# CustomESP32V2.net
KiCad netlist of a schematic drawn in Altium Designer
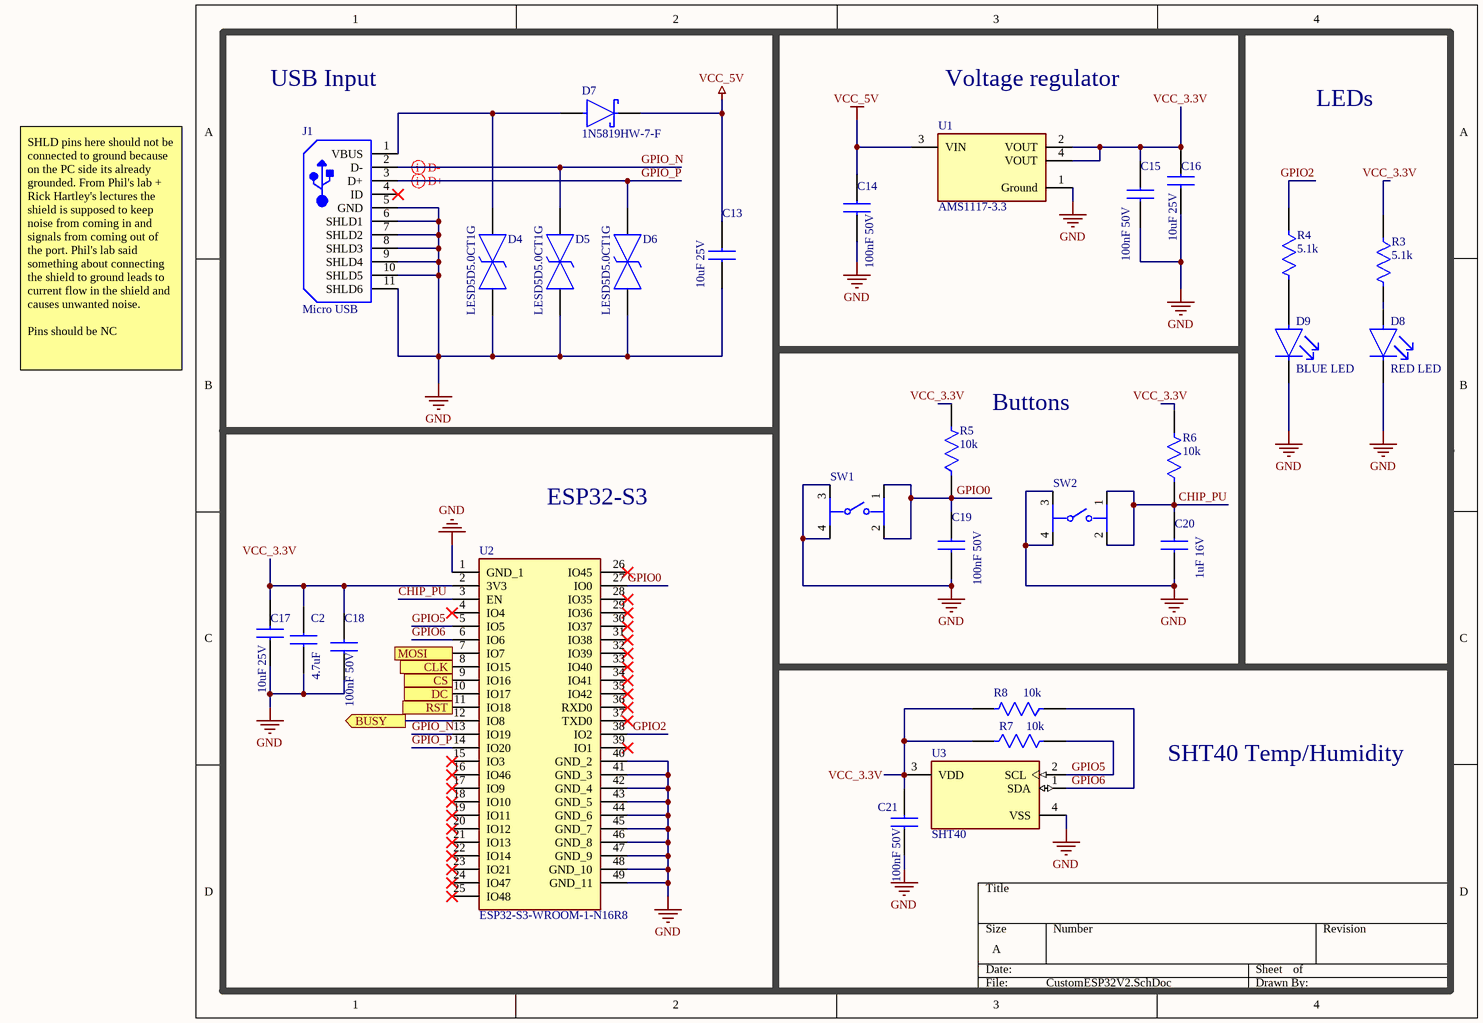
[diagram p0: CustomESP32V2.SchDoc]

(export (version "E")
  (design (tool "Eeschema 10.0.6"))
  (components
    (comp (ref "C2")
      (value "4.7uF")
      (footprint "SamacSys:CAPC1608X90N")
      (description "Capacitor")
      (fields
        (field (name "MANUFACTURER_PART_NUMBER") "CL10A475KO8NNNC")
        (field (name "MOUSER PART NUMBER") "187-CL10A475KO8NNNC")
      )
      (libsource (lib "*") (part "CL10A475KO8NNNC"))
    )
    (comp (ref "C13")
      (value "10uF 25V")
      (footprint "SamacSys:CAPC2012X145N")
      (description "Cap Ceramic 10uF 25V X5R 10% SMD 0805 85C Embossed T/R")
      (fields
        (field (name "MANUFACTURER_PART_NUMBER") "CL21A106KAYNNNG")
        (field (name "MOUSER PART NUMBER") "187-CL21A106KAYNNNG")
      )
      (libsource (lib "Integrated_Library1") (part "CL21A106KAYNNNG"))
    )
    (comp (ref "C14")
      (value "100nF 50V")
      (footprint "CAPC1608X90N")
      (fields
        (field (name "MANUFACTURER_PART_NUMBER") "GRM188R71H104KA93D")
        (field (name "MOUSER PART NUMBER") "81-GRM39X104K50D")
      )
      (libsource (lib "Integrated_Library1") (part "GRM188R71H104KA93D"))
    )
    (comp (ref "C15")
      (value "100nF 50V")
      (footprint "CAPC1608X90N")
      (fields
        (field (name "MANUFACTURER_PART_NUMBER") "GRM188R71H104KA93D")
        (field (name "MOUSER PART NUMBER") "81-GRM39X104K50D")
      )
      (libsource (lib "Integrated_Library1") (part "GRM188R71H104KA93D"))
    )
    (comp (ref "C16")
      (value "10uF 25V")
      (footprint "SamacSys:CAPC2012X145N")
      (description "Cap Ceramic 10uF 25V X5R 10% SMD 0805 85C Embossed T/R")
      (fields
        (field (name "MANUFACTURER_PART_NUMBER") "CL21A106KAYNNNG")
        (field (name "MOUSER PART NUMBER") "187-CL21A106KAYNNNG")
      )
      (libsource (lib "Integrated_Library1") (part "CL21A106KAYNNNG"))
    )
    (comp (ref "C17")
      (value "10uF 25V")
      (footprint "SamacSys:CAPC2012X145N")
      (description "Cap Ceramic 10uF 25V X5R 10% SMD 0805 85C Embossed T/R")
      (fields
        (field (name "MANUFACTURER_PART_NUMBER") "CL21A106KAYNNNG")
        (field (name "MOUSER PART NUMBER") "187-CL21A106KAYNNNG")
      )
      (libsource (lib "Integrated_Library1") (part "CL21A106KAYNNNG"))
    )
    (comp (ref "C18")
      (value "100nF 50V")
      (footprint "CAPC1608X90N")
      (fields
        (field (name "MANUFACTURER_PART_NUMBER") "GRM188R71H104KA93D")
        (field (name "MOUSER PART NUMBER") "81-GRM39X104K50D")
      )
      (libsource (lib "Integrated_Library1") (part "GRM188R71H104KA93D"))
    )
    (comp (ref "C19")
      (value "100nF 50V")
      (footprint "CAPC1608X90N")
      (fields
        (field (name "MANUFACTURER_PART_NUMBER") "GRM188R71H104KA93D")
        (field (name "MOUSER PART NUMBER") "81-GRM39X104K50D")
      )
      (libsource (lib "Integrated_Library1") (part "GRM188R71H104KA93D"))
    )
    (comp (ref "C20")
      (value "1uF 16V")
      (footprint "CAPC1608X90N")
      (fields
        (field (name "MANUFACTURER_PART_NUMBER") "CL10A105KO8NNNC")
        (field (name "MOUSER PART NUMBER") "187-CL10A105KO8NNNC")
      )
      (libsource (lib "Integrated_Library1") (part "CL10A105KO8NNNC"))
    )
    (comp (ref "C21")
      (value "100nF 50V")
      (footprint "CAPC1608X90N")
      (fields
        (field (name "MANUFACTURER_PART_NUMBER") "GRM188R71H104KA93D")
        (field (name "MOUSER PART NUMBER") "81-GRM39X104K50D")
      )
      (libsource (lib "Integrated_Library1") (part "GRM188R71H104KA93D"))
    )
    (comp (ref "D4")
      (value "LESD5D5.0CT1G")
      (footprint "SamacSys:LESD5D50CT1G")
      (description "TVS Diode (Bi-directional)")
      (libsource (lib "*") (part "LESD5D5.0CT1G"))
    )
    (comp (ref "D5")
      (value "LESD5D5.0CT1G")
      (footprint "SamacSys:LESD5D50CT1G")
      (description "TVS Diode (Bi-directional)")
      (libsource (lib "*") (part "LESD5D5.0CT1G"))
    )
    (comp (ref "D6")
      (value "LESD5D5.0CT1G")
      (footprint "SamacSys:LESD5D50CT1G")
      (description "TVS Diode (Bi-directional)")
      (libsource (lib "*") (part "LESD5D5.0CT1G"))
    )
    (comp (ref "D7")
      (value "1N5819HW-7-F")
      (footprint "FP-SOD123-IPC_A")
      (description "DIODE SCHOTTKY 40V 1A SOD123")
      (libsource (lib "Altium Content Vault") (part "1d6ec82d83fb6aee721767c19dac4b9"))
    )
    (comp (ref "D8")
      (value "RED LED")
      (footprint "FP-6_541-5092_01-4-MFG")
      (description "LED RED 0603 SMD")
      (fields
        (field (name "MANUFACTURER") "Vishay")
        (field (name "MANUFACTURER PART NUMBER") "VLMS1300-GS08")
      )
      (libsource (lib "Altium Content Vault") (part "8706943c75ba83719d021d2fdc84c58"))
    )
    (comp (ref "D9")
      (value "BLUE LED")
      (footprint "FP-6_541-5094_01-4-MFG")
      (description "LED BLUE 0603 SMD")
      (fields
        (field (name "MANUFACTURER PART NUMBER") "VLMB1300-GS08")
        (field (name "MANUFACTURER") "Vishay Semiconductor Opto Division")
      )
      (libsource (lib "Altium Content Vault") (part "8706943c75ba83719d021d2fdc84c58"))
    )
    (comp (ref "J1")
      (value "Micro USB")
      (footprint "USB-MICRO-B_V")
      (fields (field (name "MANUFACTURER") "Molex"))
      (libsource (lib "Altium Content Vault") (part "USB-5-6SHLD"))
    )
    (comp (ref "R3")
      (value "5.1k")
      (footprint "FP-CRCW0603-e3-MFG")
      (description "RES Thick Film, 5.1kΩ, 1%, 0.1W, 100ppm/°C, 0603")
      (fields (field (name "TOLERANCE") "1%"))
      (libsource (lib "Altium Content Vault") (part "1029c3af85768c4190bb7ad29bc67b5"))
    )
    (comp (ref "R4")
      (value "5.1k")
      (footprint "FP-CRCW0603-e3-MFG")
      (description "RES Thick Film, 5.1kΩ, 1%, 0.1W, 100ppm/°C, 0603")
      (fields (field (name "TOLERANCE") "1%"))
      (libsource (lib "Altium Content Vault") (part "1029c3af85768c4190bb7ad29bc67b5"))
    )
    (comp (ref "R5")
      (value "10k")
      (footprint "FP-RC1608-MFG")
      (description "Res Thick Film 0603 10kΩ 1% 0.1W ±100ppm/°C Molded SMD T/R")
      (fields (field (name "TOLERANCE") "1%"))
      (libsource (lib "Altium Content Vault") (part "1029c3af85768c4190bb7ad29bc67b5"))
    )
    (comp (ref "R6")
      (value "10k")
      (footprint "FP-RC1608-MFG")
      (description "Res Thick Film 0603 10kΩ 1% 0.1W ±100ppm/°C Molded SMD T/R")
      (fields (field (name "TOLERANCE") "1%"))
      (libsource (lib "Altium Content Vault") (part "1029c3af85768c4190bb7ad29bc67b5"))
    )
    (comp (ref "R7")
      (value "10k")
      (footprint "FP-RC1608-MFG")
      (description "Res Thick Film 0603 10kΩ 1% 0.1W ±100ppm/°C Molded SMD T/R")
      (fields (field (name "TOLERANCE") "1%"))
      (libsource (lib "Altium Content Vault") (part "1029c3af85768c4190bb7ad29bc67b5"))
    )
    (comp (ref "R8")
      (value "10k")
      (footprint "FP-RC1608-MFG")
      (description "Res Thick Film 0603 10kΩ 1% 0.1W ±100ppm/°C Molded SMD T/R")
      (fields (field (name "TOLERANCE") "1%"))
      (libsource (lib "Altium Content Vault") (part "1029c3af85768c4190bb7ad29bc67b5"))
    )
    (comp (ref "SW1")
      (value "PTS810SJM250SMTRLFS")
      (footprint "FP-PTS810SJM250SMTRLFS-MFG")
      (description "SWITCH TACTILE SPST-NO 0.05A 16V")
      (libsource (lib "Altium Content Vault") (part "1adf0dd01260c80cf25a44bfd6b99ba"))
    )
    (comp (ref "SW2")
      (value "PTS810SJM250SMTRLFS")
      (footprint "FP-PTS810SJM250SMTRLFS-MFG")
      (description "SWITCH TACTILE SPST-NO 0.05A 16V")
      (libsource (lib "Altium Content Vault") (part "1adf0dd01260c80cf25a44bfd6b99ba"))
    )
    (comp (ref "U1")
      (value "AMS1117-3.3")
      (footprint "FP-AMS1117-IPC_C")
      (description "LDO Voltage Regulators 1A, 3.3V")
      (fields
        (field (name "OCTOPART") "https://octopart.com/ams1117-3.3-advanced+monolithic+systems-25899300")
        (field (name "MANUFACTURER") "Advanced Monolithic Systems")
      )
      (libsource (lib "Altium Content Vault") (part "8bdbb5f8e77002000e30dd2845d0354"))
    )
    (comp (ref "U2")
      (value "ESP32-S3-WROOM-1-N16R8")
      (footprint "SamacSys:ESP32S3WROOM1N16R8")
      (description "Integrated Circuit")
      (fields (field (name "MOUSER PART NUMBER") "356-ESP32S3WRM1N16R8"))
      (libsource (lib "*") (part "ESP32-S3-WROOM-1-N16R8"))
    )
    (comp (ref "U3")
      (value "SHT40")
      (footprint "FP-SHT40-AD1B-R2-MFG")
      (description "SENSOR HUMIDITY 100 RH SMD")
      (libsource (lib "Altium Content Vault") (part "985d6b895d3abb4f56b1b691ea450a8"))
    )
  )
  (nets
    (net (code "1") (name "/BUSY") (class "Default")
      (node (ref "U2") (pin "12") (pinfunction "IO8_12") (pintype "passive"))
    )
    (net (code "2") (name "/CHIP_PU") (class "Default")
      (node (ref "C20") (pin "2") (pinfunction "2_2") (pintype "passive"))
      (node (ref "R6") (pin "1") (pinfunction "1_1") (pintype "passive"))
      (node (ref "SW2") (pin "1") (pinfunction "1_1") (pintype "passive"))
      (node (ref "SW2") (pin "2") (pinfunction "2_2") (pintype "passive"))
      (node (ref "U2") (pin "3") (pinfunction "EN_3") (pintype "passive"))
    )
    (net (code "3") (name "/CLK") (class "Default")
      (node (ref "U2") (pin "8") (pinfunction "IO15_8") (pintype "passive"))
    )
    (net (code "4") (name "/CS") (class "Default")
      (node (ref "U2") (pin "9") (pinfunction "IO16_9") (pintype "passive"))
    )
    (net (code "5") (name "/DC") (class "Default")
      (node (ref "U2") (pin "10") (pinfunction "IO17_10") (pintype "passive"))
    )
    (net (code "6") (name "/GPIO0") (class "Default")
      (node (ref "C19") (pin "1") (pinfunction "1_1") (pintype "passive"))
      (node (ref "R5") (pin "1") (pinfunction "1_1") (pintype "passive"))
      (node (ref "SW1") (pin "1") (pinfunction "1_1") (pintype "passive"))
      (node (ref "SW1") (pin "2") (pinfunction "2_2") (pintype "passive"))
      (node (ref "U2") (pin "27") (pinfunction "IO0_27") (pintype "passive"))
    )
    (net (code "7") (name "/GPIO2") (class "Default")
      (node (ref "R4") (pin "1") (pinfunction "1_1") (pintype "passive"))
      (node (ref "U2") (pin "38") (pinfunction "IO2_38") (pintype "passive"))
    )
    (net (code "8") (name "/GPIO5") (class "Default")
      (node (ref "R7") (pin "2") (pinfunction "2_2") (pintype "passive"))
      (node (ref "U2") (pin "5") (pinfunction "IO5_5") (pintype "passive"))
      (node (ref "U3") (pin "2") (pinfunction "SCL_2") (pintype "input"))
    )
    (net (code "9") (name "/GPIO6") (class "Default")
      (node (ref "R8") (pin "1") (pinfunction "1_1") (pintype "passive"))
      (node (ref "U2") (pin "6") (pinfunction "IO6_6") (pintype "passive"))
      (node (ref "U3") (pin "1") (pinfunction "SDA_1") (pintype "bidirectional"))
    )
    (net (code "10") (name "/GPIO_N") (class "Default")
      (node (ref "D5") (pin "2") (pinfunction "2_2") (pintype "passive"))
      (node (ref "J1") (pin "2") (pinfunction "D-_2") (pintype "passive"))
      (node (ref "U2") (pin "13") (pinfunction "IO19_13") (pintype "passive"))
    )
    (net (code "11") (name "/GPIO_P") (class "Default")
      (node (ref "D6") (pin "2") (pinfunction "2_2") (pintype "passive"))
      (node (ref "J1") (pin "3") (pinfunction "D+_3") (pintype "passive"))
      (node (ref "U2") (pin "14") (pinfunction "IO20_14") (pintype "passive"))
    )
    (net (code "12") (name "/MOSI") (class "Default")
      (node (ref "U2") (pin "7") (pinfunction "IO7_7") (pintype "passive"))
    )
    (net (code "13") (name "/RST") (class "Default")
      (node (ref "U2") (pin "11") (pinfunction "IO18_11") (pintype "passive"))
    )
    (net (code "14") (name "/VCC_3.3V") (class "Default")
      (node (ref "C15") (pin "1") (pinfunction "1_1") (pintype "passive"))
      (node (ref "C16") (pin "1") (pinfunction "1_1") (pintype "passive"))
      (node (ref "C17") (pin "1") (pinfunction "1_1") (pintype "passive"))
      (node (ref "C18") (pin "1") (pinfunction "1_1") (pintype "passive"))
      (node (ref "C2") (pin "2") (pinfunction "2_2") (pintype "passive"))
      (node (ref "C21") (pin "2") (pinfunction "2_2") (pintype "passive"))
      (node (ref "R3") (pin "1") (pinfunction "1_1") (pintype "passive"))
      (node (ref "R5") (pin "2") (pinfunction "2_2") (pintype "passive"))
      (node (ref "R6") (pin "2") (pinfunction "2_2") (pintype "passive"))
      (node (ref "R7") (pin "1") (pinfunction "1_1") (pintype "passive"))
      (node (ref "R8") (pin "2") (pinfunction "2_2") (pintype "passive"))
      (node (ref "U1") (pin "2") (pinfunction "VOUT_2") (pintype "passive"))
      (node (ref "U1") (pin "4") (pinfunction "VOUT_4") (pintype "passive"))
      (node (ref "U2") (pin "2") (pinfunction "3V3_2") (pintype "passive"))
      (node (ref "U3") (pin "3") (pinfunction "VDD_3") (pintype "power_in"))
    )
    (net (code "15") (name "GND") (class "Default")
      (node (ref "C13") (pin "2") (pinfunction "2_2") (pintype "passive"))
      (node (ref "C14") (pin "2") (pinfunction "2_2") (pintype "passive"))
      (node (ref "C15") (pin "2") (pinfunction "2_2") (pintype "passive"))
      (node (ref "C16") (pin "2") (pinfunction "2_2") (pintype "passive"))
      (node (ref "C17") (pin "2") (pinfunction "2_2") (pintype "passive"))
      (node (ref "C18") (pin "2") (pinfunction "2_2") (pintype "passive"))
      (node (ref "C19") (pin "2") (pinfunction "2_2") (pintype "passive"))
      (node (ref "C2") (pin "1") (pinfunction "1_1") (pintype "passive"))
      (node (ref "C20") (pin "1") (pinfunction "1_1") (pintype "passive"))
      (node (ref "C21") (pin "1") (pinfunction "1_1") (pintype "passive"))
      (node (ref "D4") (pin "1") (pinfunction "1_1") (pintype "passive"))
      (node (ref "D5") (pin "1") (pinfunction "1_1") (pintype "passive"))
      (node (ref "D6") (pin "1") (pinfunction "1_1") (pintype "passive"))
      (node (ref "D8") (pin "1") (pinfunction "C_1") (pintype "passive"))
      (node (ref "D9") (pin "1") (pinfunction "C_1") (pintype "passive"))
      (node (ref "J1") (pin "10") (pinfunction "SHLD5_10") (pintype "passive"))
      (node (ref "J1") (pin "11") (pinfunction "SHLD6_11") (pintype "passive"))
      (node (ref "J1") (pin "5") (pinfunction "GND_5") (pintype "passive"))
      (node (ref "J1") (pin "6") (pinfunction "SHLD1_6") (pintype "passive"))
      (node (ref "J1") (pin "7") (pinfunction "SHLD2_7") (pintype "passive"))
      (node (ref "J1") (pin "8") (pinfunction "SHLD3_8") (pintype "passive"))
      (node (ref "J1") (pin "9") (pinfunction "SHLD4_9") (pintype "passive"))
      (node (ref "SW1") (pin "3") (pinfunction "3_3") (pintype "passive"))
      (node (ref "SW1") (pin "4") (pinfunction "4_4") (pintype "passive"))
      (node (ref "SW2") (pin "3") (pinfunction "3_3") (pintype "passive"))
      (node (ref "SW2") (pin "4") (pinfunction "4_4") (pintype "passive"))
      (node (ref "U1") (pin "1") (pinfunction "Ground_1") (pintype "power_in"))
      (node (ref "U2") (pin "1") (pinfunction "GND_1_1") (pintype "passive"))
      (node (ref "U2") (pin "40") (pinfunction "GND_2_40") (pintype "passive"))
      (node (ref "U2") (pin "41") (pinfunction "GND_3_41") (pintype "passive"))
      (node (ref "U2") (pin "42") (pinfunction "GND_4_42") (pintype "passive"))
      (node (ref "U2") (pin "43") (pinfunction "GND_5_43") (pintype "passive"))
      (node (ref "U2") (pin "44") (pinfunction "GND_6_44") (pintype "passive"))
      (node (ref "U2") (pin "45") (pinfunction "GND_7_45") (pintype "passive"))
      (node (ref "U2") (pin "46") (pinfunction "GND_8_46") (pintype "passive"))
      (node (ref "U2") (pin "47") (pinfunction "GND_9_47") (pintype "passive"))
      (node (ref "U2") (pin "48") (pinfunction "GND_10_48") (pintype "passive"))
      (node (ref "U2") (pin "49") (pinfunction "GND_11_49") (pintype "passive"))
      (node (ref "U3") (pin "4") (pinfunction "VSS_4") (pintype "power_in"))
    )
    (net (code "16") (name "Net-(D7-A)") (class "Default")
      (node (ref "D4") (pin "2") (pinfunction "2_2") (pintype "passive"))
      (node (ref "D7") (pin "2") (pinfunction "A_2") (pintype "passive"))
      (node (ref "J1") (pin "1") (pinfunction "VBUS_1") (pintype "passive"))
    )
    (net (code "17") (name "Net-(D8-A)") (class "Default")
      (node (ref "D8") (pin "2") (pinfunction "A_2") (pintype "passive"))
      (node (ref "R3") (pin "2") (pinfunction "2_2") (pintype "passive"))
    )
    (net (code "18") (name "Net-(D9-A)") (class "Default")
      (node (ref "D9") (pin "2") (pinfunction "A_2") (pintype "passive"))
      (node (ref "R4") (pin "2") (pinfunction "2_2") (pintype "passive"))
    )
    (net (code "19") (name "VCC_5V") (class "Default")
      (node (ref "C13") (pin "1") (pinfunction "1_1") (pintype "passive"))
      (node (ref "C14") (pin "1") (pinfunction "1_1") (pintype "passive"))
      (node (ref "D7") (pin "1") (pinfunction "C_1") (pintype "passive"))
      (node (ref "U1") (pin "3") (pinfunction "VIN_3") (pintype "power_in"))
    )
    (net (code "20") (name "unconnected-(J1-ID-Pad4)") (class "Default")
      (node (ref "J1") (pin "4") (pinfunction "ID_4") (pintype "passive+no_connect"))
    )
    (net (code "21") (name "unconnected-(U2-IO1-Pad39)") (class "Default")
      (node (ref "U2") (pin "39") (pinfunction "IO1_39") (pintype "passive+no_connect"))
    )
    (net (code "22") (name "unconnected-(U2-IO3-Pad15)") (class "Default")
      (node (ref "U2") (pin "15") (pinfunction "IO3_15") (pintype "passive+no_connect"))
    )
    (net (code "23") (name "unconnected-(U2-IO4-Pad4)") (class "Default")
      (node (ref "U2") (pin "4") (pinfunction "IO4_4") (pintype "passive+no_connect"))
    )
    (net (code "24") (name "unconnected-(U2-IO9-Pad17)") (class "Default")
      (node (ref "U2") (pin "17") (pinfunction "IO9_17") (pintype "passive+no_connect"))
    )
    (net (code "25") (name "unconnected-(U2-IO10-Pad18)") (class "Default")
      (node (ref "U2") (pin "18") (pinfunction "IO10_18") (pintype "passive+no_connect"))
    )
    (net (code "26") (name "unconnected-(U2-IO11-Pad19)") (class "Default")
      (node (ref "U2") (pin "19") (pinfunction "IO11_19") (pintype "passive+no_connect"))
    )
    (net (code "27") (name "unconnected-(U2-IO12-Pad20)") (class "Default")
      (node (ref "U2") (pin "20") (pinfunction "IO12_20") (pintype "passive+no_connect"))
    )
    (net (code "28") (name "unconnected-(U2-IO13-Pad21)") (class "Default")
      (node (ref "U2") (pin "21") (pinfunction "IO13_21") (pintype "passive+no_connect"))
    )
    (net (code "29") (name "unconnected-(U2-IO14-Pad22)") (class "Default")
      (node (ref "U2") (pin "22") (pinfunction "IO14_22") (pintype "passive+no_connect"))
    )
    (net (code "30") (name "unconnected-(U2-IO21-Pad23)") (class "Default")
      (node (ref "U2") (pin "23") (pinfunction "IO21_23") (pintype "passive+no_connect"))
    )
    (net (code "31") (name "unconnected-(U2-IO35-Pad28)") (class "Default")
      (node (ref "U2") (pin "28") (pinfunction "IO35_28") (pintype "passive+no_connect"))
    )
    (net (code "32") (name "unconnected-(U2-IO36-Pad29)") (class "Default")
      (node (ref "U2") (pin "29") (pinfunction "IO36_29") (pintype "passive+no_connect"))
    )
    (net (code "33") (name "unconnected-(U2-IO37-Pad30)") (class "Default")
      (node (ref "U2") (pin "30") (pinfunction "IO37_30") (pintype "passive+no_connect"))
    )
    (net (code "34") (name "unconnected-(U2-IO38-Pad31)") (class "Default")
      (node (ref "U2") (pin "31") (pinfunction "IO38_31") (pintype "passive+no_connect"))
    )
    (net (code "35") (name "unconnected-(U2-IO39-Pad32)") (class "Default")
      (node (ref "U2") (pin "32") (pinfunction "IO39_32") (pintype "passive+no_connect"))
    )
    (net (code "36") (name "unconnected-(U2-IO40-Pad33)") (class "Default")
      (node (ref "U2") (pin "33") (pinfunction "IO40_33") (pintype "passive+no_connect"))
    )
    (net (code "37") (name "unconnected-(U2-IO41-Pad34)") (class "Default")
      (node (ref "U2") (pin "34") (pinfunction "IO41_34") (pintype "passive+no_connect"))
    )
    (net (code "38") (name "unconnected-(U2-IO42-Pad35)") (class "Default")
      (node (ref "U2") (pin "35") (pinfunction "IO42_35") (pintype "passive+no_connect"))
    )
    (net (code "39") (name "unconnected-(U2-IO45-Pad26)") (class "Default")
      (node (ref "U2") (pin "26") (pinfunction "IO45_26") (pintype "passive+no_connect"))
    )
    (net (code "40") (name "unconnected-(U2-IO46-Pad16)") (class "Default")
      (node (ref "U2") (pin "16") (pinfunction "IO46_16") (pintype "passive+no_connect"))
    )
    (net (code "41") (name "unconnected-(U2-IO47-Pad24)") (class "Default")
      (node (ref "U2") (pin "24") (pinfunction "IO47_24") (pintype "passive+no_connect"))
    )
    (net (code "42") (name "unconnected-(U2-IO48-Pad25)") (class "Default")
      (node (ref "U2") (pin "25") (pinfunction "IO48_25") (pintype "passive+no_connect"))
    )
    (net (code "43") (name "unconnected-(U2-RXD0-Pad36)") (class "Default")
      (node (ref "U2") (pin "36") (pinfunction "RXD0_36") (pintype "passive+no_connect"))
    )
    (net (code "44") (name "unconnected-(U2-TXD0-Pad37)") (class "Default")
      (node (ref "U2") (pin "37") (pinfunction "TXD0_37") (pintype "passive+no_connect"))
    )
  )
)
